# hackerstacker_mainboard.net
KiCad netlist of a schematic drawn in EAGLE
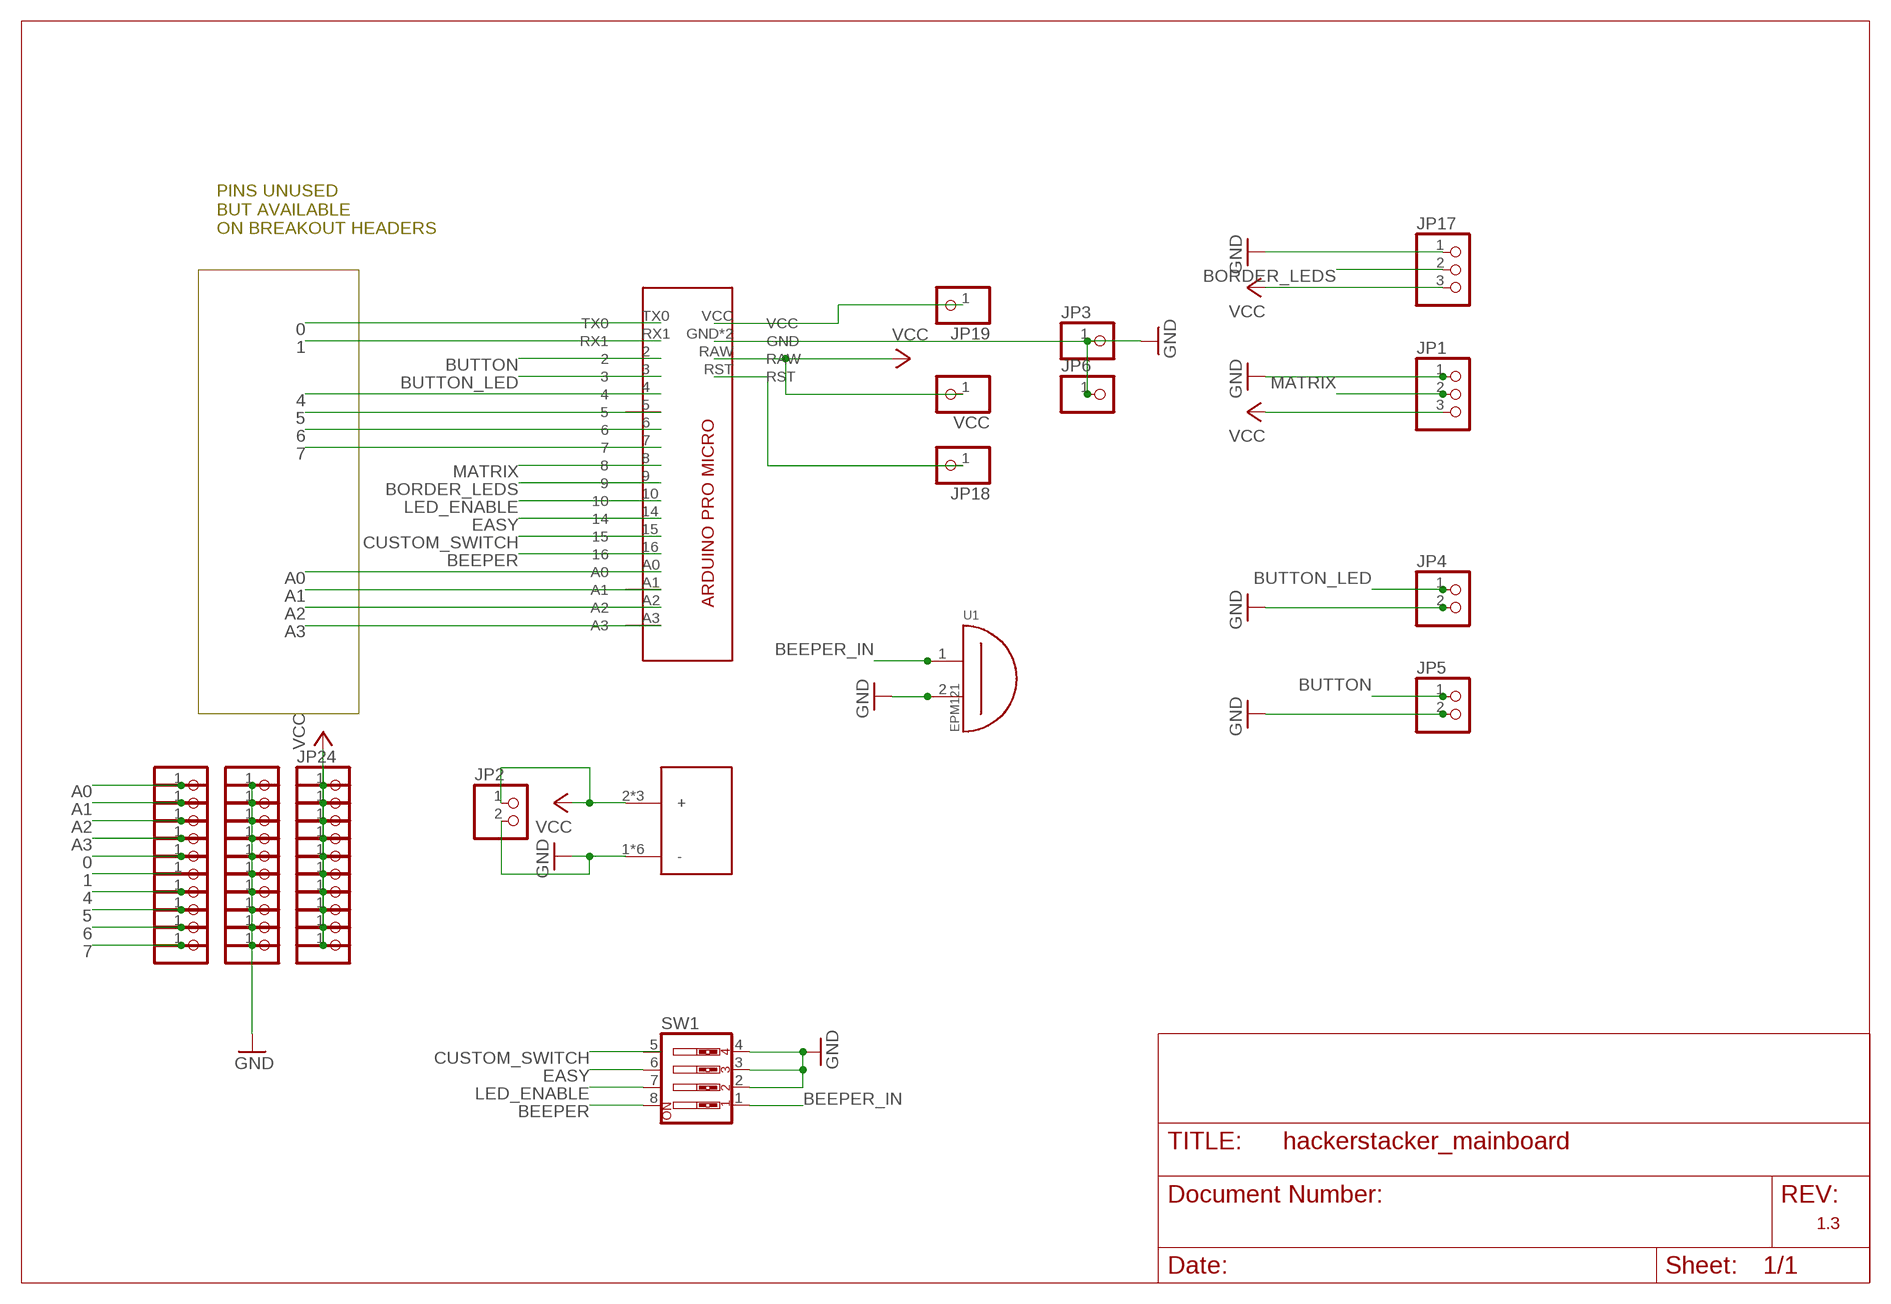
[diagram p0: schematic, sheet 1]

(export (version "E")
  (design (tool "Eeschema 10.0.6"))
  (components
    (comp (ref "JP1")
      (value "PINHD-1X3")
      (footprint "eagle-import:1X03")
      (libsource (lib "eagle-import") (part "PINHD-1X3"))
    )
    (comp (ref "JP2")
      (value "PINHD-1X2")
      (footprint "eagle-import:1X02")
      (libsource (lib "eagle-import") (part "PINHD-1X2"))
    )
    (comp (ref "JP3")
      (value "PINHD-1X1CB")
      (footprint "eagle-import:1X01-CLEANBIG")
      (libsource (lib "eagle-import") (part "PINHD-1X1CB"))
    )
    (comp (ref "JP4")
      (value "PINHD-1X2")
      (footprint "eagle-import:1X02")
      (libsource (lib "eagle-import") (part "PINHD-1X2"))
    )
    (comp (ref "JP5")
      (value "PINHD-1X2")
      (footprint "eagle-import:1X02")
      (libsource (lib "eagle-import") (part "PINHD-1X2"))
    )
    (comp (ref "JP6")
      (value "PINHD-1X1CB")
      (footprint "eagle-import:1X01-CLEANBIG")
      (libsource (lib "eagle-import") (part "PINHD-1X1CB"))
    )
    (comp (ref "JP7")
      (value "PINHD-1X1CB")
      (footprint "eagle-import:1X01-CLEANBIG")
      (libsource (lib "eagle-import") (part "PINHD-1X1CB"))
    )
    (comp (ref "JP8")
      (value "PINHD-1X1CB")
      (footprint "eagle-import:1X01-CLEANBIG")
      (libsource (lib "eagle-import") (part "PINHD-1X1CB"))
    )
    (comp (ref "JP9")
      (value "PINHD-1X1CB")
      (footprint "eagle-import:1X01-CLEANBIG")
      (libsource (lib "eagle-import") (part "PINHD-1X1CB"))
    )
    (comp (ref "JP10")
      (value "PINHD-1X1CB")
      (footprint "eagle-import:1X01-CLEANBIG")
      (libsource (lib "eagle-import") (part "PINHD-1X1CB"))
    )
    (comp (ref "JP11")
      (value "PINHD-1X1CB")
      (footprint "eagle-import:1X01-CLEANBIG")
      (libsource (lib "eagle-import") (part "PINHD-1X1CB"))
    )
    (comp (ref "JP12")
      (value "PINHD-1X1CB")
      (footprint "eagle-import:1X01-CLEANBIG")
      (libsource (lib "eagle-import") (part "PINHD-1X1CB"))
    )
    (comp (ref "JP13")
      (value "PINHD-1X1CB")
      (footprint "eagle-import:1X01-CLEANBIG")
      (libsource (lib "eagle-import") (part "PINHD-1X1CB"))
    )
    (comp (ref "JP14")
      (value "PINHD-1X1CB")
      (footprint "eagle-import:1X01-CLEANBIG")
      (libsource (lib "eagle-import") (part "PINHD-1X1CB"))
    )
    (comp (ref "JP15")
      (value "PINHD-1X1CB")
      (footprint "eagle-import:1X01-CLEANBIG")
      (libsource (lib "eagle-import") (part "PINHD-1X1CB"))
    )
    (comp (ref "JP16")
      (value "PINHD-1X1CB")
      (footprint "eagle-import:1X01-CLEANBIG")
      (libsource (lib "eagle-import") (part "PINHD-1X1CB"))
    )
    (comp (ref "JP17")
      (value "PINHD-1X3")
      (footprint "eagle-import:1X03")
      (libsource (lib "eagle-import") (part "PINHD-1X3"))
    )
    (comp (ref "JP18")
      (value "PINHD-1X1CB")
      (footprint "eagle-import:1X01-CLEANBIG")
      (libsource (lib "eagle-import") (part "PINHD-1X1CB"))
    )
    (comp (ref "JP19")
      (value "PINHD-1X1CB")
      (footprint "eagle-import:1X01-CLEANBIG")
      (libsource (lib "eagle-import") (part "PINHD-1X1CB"))
    )
    (comp (ref "JP20")
      (value "PINHD-1X1CB")
      (footprint "eagle-import:1X01-CLEANBIG")
      (libsource (lib "eagle-import") (part "PINHD-1X1CB"))
    )
    (comp (ref "JP21")
      (value "PINHD-1X1CB")
      (footprint "eagle-import:1X01-CLEANBIG")
      (libsource (lib "eagle-import") (part "PINHD-1X1CB"))
    )
    (comp (ref "JP22")
      (value "PINHD-1X1CB")
      (footprint "eagle-import:1X01-CLEANBIG")
      (libsource (lib "eagle-import") (part "PINHD-1X1CB"))
    )
    (comp (ref "JP23")
      (value "PINHD-1X1CB")
      (footprint "eagle-import:1X01-CLEANBIG")
      (libsource (lib "eagle-import") (part "PINHD-1X1CB"))
    )
    (comp (ref "JP24")
      (value "PINHD-1X1CB")
      (footprint "eagle-import:1X01-CLEANBIG")
      (libsource (lib "eagle-import") (part "PINHD-1X1CB"))
    )
    (comp (ref "JP25")
      (value "PINHD-1X1CB")
      (footprint "eagle-import:1X01-CLEANBIG")
      (libsource (lib "eagle-import") (part "PINHD-1X1CB"))
    )
    (comp (ref "JP26")
      (value "PINHD-1X1CB")
      (footprint "eagle-import:1X01-CLEANBIG")
      (libsource (lib "eagle-import") (part "PINHD-1X1CB"))
    )
    (comp (ref "JP27")
      (value "PINHD-1X1CB")
      (footprint "eagle-import:1X01-CLEANBIG")
      (libsource (lib "eagle-import") (part "PINHD-1X1CB"))
    )
    (comp (ref "JP28")
      (value "PINHD-1X1CB")
      (footprint "eagle-import:1X01-CLEANBIG")
      (libsource (lib "eagle-import") (part "PINHD-1X1CB"))
    )
    (comp (ref "JP29")
      (value "PINHD-1X1CB")
      (footprint "eagle-import:1X01-CLEANBIG")
      (libsource (lib "eagle-import") (part "PINHD-1X1CB"))
    )
    (comp (ref "JP30")
      (value "PINHD-1X1CB")
      (footprint "eagle-import:1X01-CLEANBIG")
      (libsource (lib "eagle-import") (part "PINHD-1X1CB"))
    )
    (comp (ref "JP31")
      (value "PINHD-1X1CB")
      (footprint "eagle-import:1X01-CLEANBIG")
      (libsource (lib "eagle-import") (part "PINHD-1X1CB"))
    )
    (comp (ref "JP32")
      (value "PINHD-1X1CB")
      (footprint "eagle-import:1X01-CLEANBIG")
      (libsource (lib "eagle-import") (part "PINHD-1X1CB"))
    )
    (comp (ref "JP33")
      (value "PINHD-1X1CB")
      (footprint "eagle-import:1X01-CLEANBIG")
      (libsource (lib "eagle-import") (part "PINHD-1X1CB"))
    )
    (comp (ref "JP34")
      (value "PINHD-1X1CB")
      (footprint "eagle-import:1X01-CLEANBIG")
      (libsource (lib "eagle-import") (part "PINHD-1X1CB"))
    )
    (comp (ref "JP35")
      (value "PINHD-1X1CB")
      (footprint "eagle-import:1X01-CLEANBIG")
      (libsource (lib "eagle-import") (part "PINHD-1X1CB"))
    )
    (comp (ref "JP36")
      (value "PINHD-1X1CB")
      (footprint "eagle-import:1X01-CLEANBIG")
      (libsource (lib "eagle-import") (part "PINHD-1X1CB"))
    )
    (comp (ref "JP37")
      (value "PINHD-1X1CB")
      (footprint "eagle-import:1X01-CLEANBIG")
      (libsource (lib "eagle-import") (part "PINHD-1X1CB"))
    )
    (comp (ref "JP38")
      (value "PINHD-1X1CB")
      (footprint "eagle-import:1X01-CLEANBIG")
      (libsource (lib "eagle-import") (part "PINHD-1X1CB"))
    )
    (comp (ref "JP39")
      (value "PINHD-1X1CB")
      (footprint "eagle-import:1X01-CLEANBIG")
      (libsource (lib "eagle-import") (part "PINHD-1X1CB"))
    )
    (comp (ref "SW1")
      (value "SW_DIP-4")
      (footprint "eagle-import:EDG-04")
      (libsource (lib "eagle-import") (part "SW_DIP-4"))
    )
    (comp (ref "U$1")
      (value "ARDUINO_PRO_MICRO")
      (footprint "eagle-import:APM_PAC")
      (libsource (lib "eagle-import") (part "ARDUINO_PRO_MICRO"))
    )
    (comp (ref "U$3")
      (value "2.1MMARDUINOPOERJACK")
      (footprint "eagle-import:POWERSUPPLY_DC-21MM")
      (libsource (lib "eagle-import") (part "2.1MMARDUINOPOERJACK"))
    )
    (comp (ref "U1")
      (value "EPM121")
      (footprint "eagle-import:EPM121")
      (libsource (lib "eagle-import") (part "EPM121"))
    )
    (comp (ref "VCC")
      (value "PINHD-1X1CB")
      (footprint "eagle-import:1X01-CLEANBIG")
      (libsource (lib "eagle-import") (part "PINHD-1X1CB"))
    )
  )
  (nets
    (net (code "1") (name "/0") (class "Default")
      (node (ref "JP11") (pin "1") (pinfunction "1_1") (pintype "passive"))
      (node (ref "U$1") (pin "TX0") (pinfunction "TX0_TX0") (pintype "bidirectional"))
    )
    (net (code "2") (name "/1") (class "Default")
      (node (ref "JP12") (pin "1") (pinfunction "1_1") (pintype "passive"))
      (node (ref "U$1") (pin "RX1") (pinfunction "RX1_RX1") (pintype "bidirectional"))
    )
    (net (code "3") (name "/4") (class "Default")
      (node (ref "JP13") (pin "1") (pinfunction "1_1") (pintype "passive"))
      (node (ref "U$1") (pin "4") (pinfunction "4_4") (pintype "bidirectional"))
    )
    (net (code "4") (name "/5") (class "Default")
      (node (ref "JP37") (pin "1") (pinfunction "1_1") (pintype "passive"))
      (node (ref "U$1") (pin "5") (pinfunction "5_5") (pintype "bidirectional"))
    )
    (net (code "5") (name "/6") (class "Default")
      (node (ref "JP38") (pin "1") (pinfunction "1_1") (pintype "passive"))
      (node (ref "U$1") (pin "6") (pinfunction "6_6") (pintype "bidirectional"))
    )
    (net (code "6") (name "/7") (class "Default")
      (node (ref "JP39") (pin "1") (pinfunction "1_1") (pintype "passive"))
      (node (ref "U$1") (pin "7") (pinfunction "7_7") (pintype "bidirectional"))
    )
    (net (code "7") (name "/A0") (class "Default")
      (node (ref "JP7") (pin "1") (pinfunction "1_1") (pintype "passive"))
      (node (ref "U$1") (pin "A0") (pinfunction "A0_A0") (pintype "bidirectional"))
    )
    (net (code "8") (name "/A1") (class "Default")
      (node (ref "JP8") (pin "1") (pinfunction "1_1") (pintype "passive"))
      (node (ref "U$1") (pin "A1") (pinfunction "A1_A1") (pintype "bidirectional"))
    )
    (net (code "9") (name "/A2") (class "Default")
      (node (ref "JP9") (pin "1") (pinfunction "1_1") (pintype "passive"))
      (node (ref "U$1") (pin "A2") (pinfunction "A2_A2") (pintype "bidirectional"))
    )
    (net (code "10") (name "/A3") (class "Default")
      (node (ref "JP31") (pin "1") (pinfunction "1_1") (pintype "passive"))
      (node (ref "U$1") (pin "A3") (pinfunction "A3_A3") (pintype "bidirectional"))
    )
    (net (code "11") (name "/BEEPER") (class "Default")
      (node (ref "SW1") (pin "8") (pinfunction "8_8") (pintype "passive"))
      (node (ref "U$1") (pin "16") (pinfunction "16_16") (pintype "bidirectional"))
    )
    (net (code "12") (name "/BEEPER_IN") (class "Default")
      (node (ref "SW1") (pin "1") (pinfunction "1_1") (pintype "passive"))
      (node (ref "U1") (pin "1") (pinfunction "P$1_1") (pintype "bidirectional"))
    )
    (net (code "13") (name "/BORDER_LEDS") (class "Default")
      (node (ref "JP17") (pin "2") (pinfunction "2_2") (pintype "passive"))
      (node (ref "U$1") (pin "9") (pinfunction "9_9") (pintype "bidirectional"))
    )
    (net (code "14") (name "/BUTTON") (class "Default")
      (node (ref "JP5") (pin "1") (pinfunction "1_1") (pintype "passive"))
      (node (ref "U$1") (pin "2") (pinfunction "2_2") (pintype "bidirectional"))
    )
    (net (code "15") (name "/BUTTON_LED") (class "Default")
      (node (ref "JP4") (pin "1") (pinfunction "1_1") (pintype "passive"))
      (node (ref "U$1") (pin "3") (pinfunction "3_3") (pintype "bidirectional"))
    )
    (net (code "16") (name "/CUSTOM_SWITCH") (class "Default")
      (node (ref "SW1") (pin "5") (pinfunction "5_5") (pintype "passive"))
      (node (ref "U$1") (pin "15") (pinfunction "15_15") (pintype "bidirectional"))
    )
    (net (code "17") (name "/EASY") (class "Default")
      (node (ref "SW1") (pin "6") (pinfunction "6_6") (pintype "passive"))
      (node (ref "U$1") (pin "14") (pinfunction "14_14") (pintype "bidirectional"))
    )
    (net (code "18") (name "/LED_ENABLE") (class "Default")
      (node (ref "SW1") (pin "7") (pinfunction "7_7") (pintype "passive"))
      (node (ref "U$1") (pin "10") (pinfunction "10_10") (pintype "bidirectional"))
    )
    (net (code "19") (name "/MATRIX") (class "Default")
      (node (ref "JP1") (pin "2") (pinfunction "2_2") (pintype "passive"))
      (node (ref "U$1") (pin "8") (pinfunction "8_8") (pintype "bidirectional"))
    )
    (net (code "20") (name "GND") (class "Default")
      (node (ref "JP1") (pin "1") (pinfunction "1_1") (pintype "passive"))
      (node (ref "JP14") (pin "1") (pinfunction "1_1") (pintype "passive"))
      (node (ref "JP15") (pin "1") (pinfunction "1_1") (pintype "passive"))
      (node (ref "JP16") (pin "1") (pinfunction "1_1") (pintype "passive"))
      (node (ref "JP17") (pin "1") (pinfunction "1_1") (pintype "passive"))
      (node (ref "JP2") (pin "2") (pinfunction "2_2") (pintype "passive"))
      (node (ref "JP20") (pin "1") (pinfunction "1_1") (pintype "passive"))
      (node (ref "JP21") (pin "1") (pinfunction "1_1") (pintype "passive"))
      (node (ref "JP22") (pin "1") (pinfunction "1_1") (pintype "passive"))
      (node (ref "JP23") (pin "1") (pinfunction "1_1") (pintype "passive"))
      (node (ref "JP3") (pin "1") (pinfunction "1_1") (pintype "passive"))
      (node (ref "JP34") (pin "1") (pinfunction "1_1") (pintype "passive"))
      (node (ref "JP35") (pin "1") (pinfunction "1_1") (pintype "passive"))
      (node (ref "JP36") (pin "1") (pinfunction "1_1") (pintype "passive"))
      (node (ref "JP4") (pin "2") (pinfunction "2_2") (pintype "passive"))
      (node (ref "JP5") (pin "2") (pinfunction "2_2") (pintype "passive"))
      (node (ref "JP6") (pin "1") (pinfunction "1_1") (pintype "passive"))
      (node (ref "SW1") (pin "2") (pinfunction "2_2") (pintype "passive"))
      (node (ref "SW1") (pin "3") (pinfunction "3_3") (pintype "passive"))
      (node (ref "SW1") (pin "4") (pinfunction "4_4") (pintype "passive"))
      (node (ref "U$1") (pin "GND") (pinfunction "GND_GND") (pintype "bidirectional"))
      (node (ref "U$1") (pin "GND2") (pinfunction "GND_GND2") (pintype "bidirectional"))
      (node (ref "U$3") (pin "1") (pinfunction "-_1") (pintype "bidirectional"))
      (node (ref "U$3") (pin "3") (pinfunction "-_3") (pintype "bidirectional"))
      (node (ref "U$3") (pin "4") (pinfunction "-_4") (pintype "bidirectional"))
      (node (ref "U$3") (pin "5") (pinfunction "-_5") (pintype "bidirectional"))
      (node (ref "U$3") (pin "6") (pinfunction "-_6") (pintype "bidirectional"))
      (node (ref "U$3") (pin "7") (pinfunction "-_7") (pintype "bidirectional"))
      (node (ref "U1") (pin "2") (pinfunction "P$2_2") (pintype "bidirectional"))
    )
    (net (code "21") (name "Net-(JP18-Pad1)") (class "Default")
      (node (ref "JP18") (pin "1") (pinfunction "1_1") (pintype "passive"))
      (node (ref "U$1") (pin "RST") (pinfunction "RST_RST") (pintype "bidirectional"))
    )
    (net (code "22") (name "Net-(JP19-Pad1)") (class "Default")
      (node (ref "JP19") (pin "1") (pinfunction "1_1") (pintype "passive"))
      (node (ref "U$1") (pin "VCC") (pinfunction "VCC_VCC") (pintype "bidirectional"))
    )
    (net (code "23") (name "VCC") (class "Default")
      (node (ref "JP1") (pin "3") (pinfunction "3_3") (pintype "passive"))
      (node (ref "JP10") (pin "1") (pinfunction "1_1") (pintype "passive"))
      (node (ref "JP17") (pin "3") (pinfunction "3_3") (pintype "passive"))
      (node (ref "JP2") (pin "1") (pinfunction "1_1") (pintype "passive"))
      (node (ref "JP24") (pin "1") (pinfunction "1_1") (pintype "passive"))
      (node (ref "JP25") (pin "1") (pinfunction "1_1") (pintype "passive"))
      (node (ref "JP26") (pin "1") (pinfunction "1_1") (pintype "passive"))
      (node (ref "JP27") (pin "1") (pinfunction "1_1") (pintype "passive"))
      (node (ref "JP28") (pin "1") (pinfunction "1_1") (pintype "passive"))
      (node (ref "JP29") (pin "1") (pinfunction "1_1") (pintype "passive"))
      (node (ref "JP30") (pin "1") (pinfunction "1_1") (pintype "passive"))
      (node (ref "JP32") (pin "1") (pinfunction "1_1") (pintype "passive"))
      (node (ref "JP33") (pin "1") (pinfunction "1_1") (pintype "passive"))
      (node (ref "U$1") (pin "RAW") (pinfunction "RAW_RAW") (pintype "bidirectional"))
      (node (ref "U$3") (pin "2") (pinfunction "+_2") (pintype "bidirectional"))
      (node (ref "U$3") (pin "8") (pinfunction "+_8") (pintype "bidirectional"))
      (node (ref "U$3") (pin "9") (pinfunction "+_9") (pintype "bidirectional"))
      (node (ref "VCC") (pin "1") (pinfunction "1_1") (pintype "passive"))
    )
  )
)
